# CM4_HDMI.net
KiCad netlist of a schematic drawn in Altium Designer
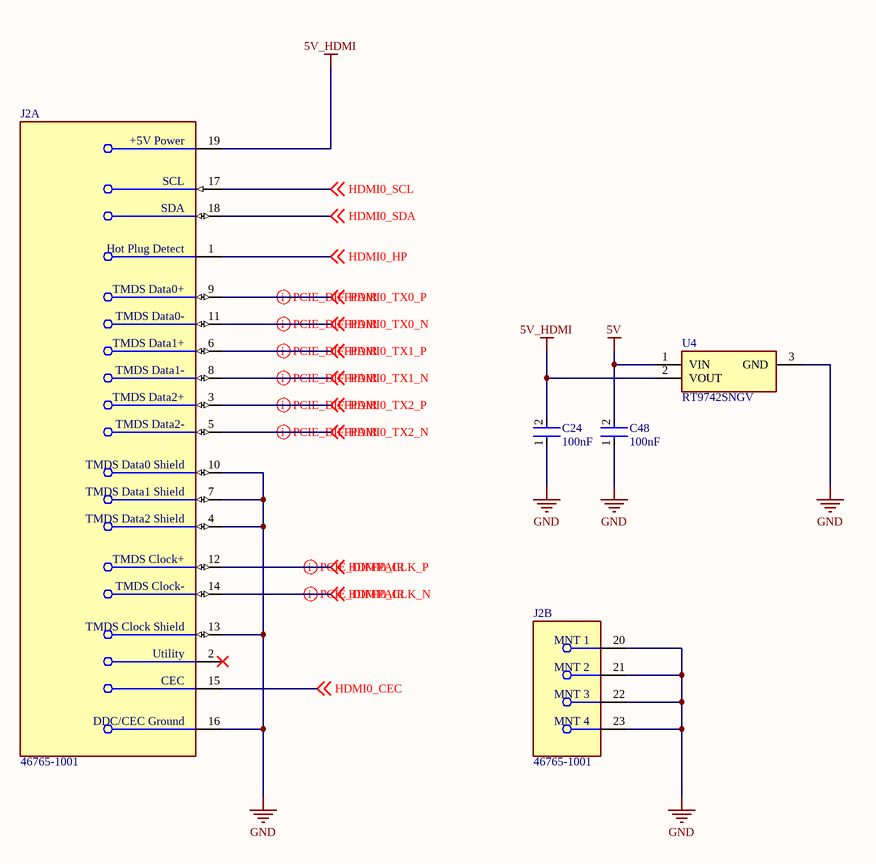
[diagram p0: CM4_HDMI.SchDoc]

(export (version "E")
  (design (tool "Eeschema 10.0.6"))
  (components
    (comp (ref "C24")
      (value "100nF")
      (footprint "FP-GRM15-MFG")
      (description "CAP CER 0.1UF 16V X7R 0402")
      (fields (field (name "MANUFACTURER PART NUMBER") "GRM155R71C104KA88D") (field (name "TOLERANCE") "10%"))
      (libsource (lib "Altium Content Vault") (part "236180d848d6139a670b325ea6854c9"))
    )
    (comp (ref "C48")
      (value "100nF")
      (footprint "FP-GRM15-MFG")
      (description "CAP CER 0.1UF 16V X7R 0402")
      (fields (field (name "MANUFACTURER PART NUMBER") "GRM155R71C104KA88D") (field (name "TOLERANCE") "10%"))
      (libsource (lib "Altium Content Vault") (part "236180d848d6139a670b325ea6854c9"))
    )
    (comp (ref "J2")
      (value "46765-1001")
      (footprint "FP-46765-1001-MFG")
      (description "CONN RCP MICRO HDMI 19POS SMD RA")
      (libsource (lib "Altium Content Vault") (part "420d22288d448ae8bfda7267695e9ff"))
    )
    (comp (ref "U4")
      (value "RT9742SNGV")
      (footprint "SamacSys:SOT95P279X130-3N")
      (description "Integrated Circuit")
      (libsource (lib "*") (part "RT9742SNGV"))
    )
  )
  (nets
    (net (code "1") (name "5V") (class "Default")
      (node (ref "C48") (pin "2") (pinfunction "2_2") (pintype "passive"))
      (node (ref "U4") (pin "1") (pinfunction "VIN_1") (pintype "passive"))
    )
    (net (code "2") (name "5V_HDMI") (class "Default")
      (node (ref "C24") (pin "2") (pinfunction "2_2") (pintype "passive"))
      (node (ref "J2") (pin "19") (pinfunction "+5V_Power_19") (pintype "power_in"))
      (node (ref "U4") (pin "2") (pinfunction "VOUT_2") (pintype "passive"))
    )
    (net (code "3") (name "GND") (class "Default")
      (node (ref "C24") (pin "1") (pinfunction "1_1") (pintype "passive"))
      (node (ref "C48") (pin "1") (pinfunction "1_1") (pintype "passive"))
      (node (ref "J2") (pin "10") (pinfunction "TMDS_Data0_Shield_10") (pintype "bidirectional"))
      (node (ref "J2") (pin "13") (pinfunction "TMDS_Clock_Shield_13") (pintype "bidirectional"))
      (node (ref "J2") (pin "16") (pinfunction "DDC/CEC_Ground_16") (pintype "passive"))
      (node (ref "J2") (pin "20") (pinfunction "MNT_1_20") (pintype "passive"))
      (node (ref "J2") (pin "21") (pinfunction "MNT_2_21") (pintype "passive"))
      (node (ref "J2") (pin "22") (pinfunction "MNT_3_22") (pintype "passive"))
      (node (ref "J2") (pin "23") (pinfunction "MNT_4_23") (pintype "passive"))
      (node (ref "J2") (pin "4") (pinfunction "TMDS_Data2_Shield_4") (pintype "bidirectional"))
      (node (ref "J2") (pin "7") (pinfunction "TMDS_Data1_Shield_7") (pintype "bidirectional"))
      (node (ref "U4") (pin "3") (pinfunction "GND_3") (pintype "passive"))
    )
    (net (code "4") (name "HDMI0_CEC") (class "Default")
      (node (ref "J2") (pin "15") (pinfunction "CEC_15") (pintype "passive"))
    )
    (net (code "5") (name "HDMI0_CLK_N") (class "Default")
      (node (ref "J2") (pin "14") (pinfunction "TMDS_Clock-_14") (pintype "bidirectional"))
    )
    (net (code "6") (name "HDMI0_CLK_P") (class "Default")
      (node (ref "J2") (pin "12") (pinfunction "TMDS_Clock+_12") (pintype "bidirectional"))
    )
    (net (code "7") (name "HDMI0_HP") (class "Default")
      (node (ref "J2") (pin "1") (pinfunction "Hot_Plug_Detect_1") (pintype "passive"))
    )
    (net (code "8") (name "HDMI0_SCL") (class "Default")
      (node (ref "J2") (pin "17") (pinfunction "SCL_17") (pintype "input"))
    )
    (net (code "9") (name "HDMI0_SDA") (class "Default")
      (node (ref "J2") (pin "18") (pinfunction "SDA_18") (pintype "bidirectional"))
    )
    (net (code "10") (name "HDMI0_TX0_N") (class "Default")
      (node (ref "J2") (pin "11") (pinfunction "TMDS_Data0-_11") (pintype "bidirectional"))
    )
    (net (code "11") (name "HDMI0_TX0_P") (class "Default")
      (node (ref "J2") (pin "9") (pinfunction "TMDS_Data0+_9") (pintype "bidirectional"))
    )
    (net (code "12") (name "HDMI0_TX1_N") (class "Default")
      (node (ref "J2") (pin "8") (pinfunction "TMDS_Data1-_8") (pintype "bidirectional"))
    )
    (net (code "13") (name "HDMI0_TX1_P") (class "Default")
      (node (ref "J2") (pin "6") (pinfunction "TMDS_Data1+_6") (pintype "bidirectional"))
    )
    (net (code "14") (name "HDMI0_TX2_N") (class "Default")
      (node (ref "J2") (pin "5") (pinfunction "TMDS_Data2-_5") (pintype "bidirectional"))
    )
    (net (code "15") (name "HDMI0_TX2_P") (class "Default")
      (node (ref "J2") (pin "3") (pinfunction "TMDS_Data2+_3") (pintype "bidirectional"))
    )
    (net (code "16") (name "unconnected-(J2A-Utility-Pad2)") (class "Default")
      (node (ref "J2") (pin "2") (pinfunction "Utility_2") (pintype "passive+no_connect"))
    )
  )
)
